# expansion_module_BLE_BMD330AR.net
KiCad netlist of a schematic drawn in EAGLE
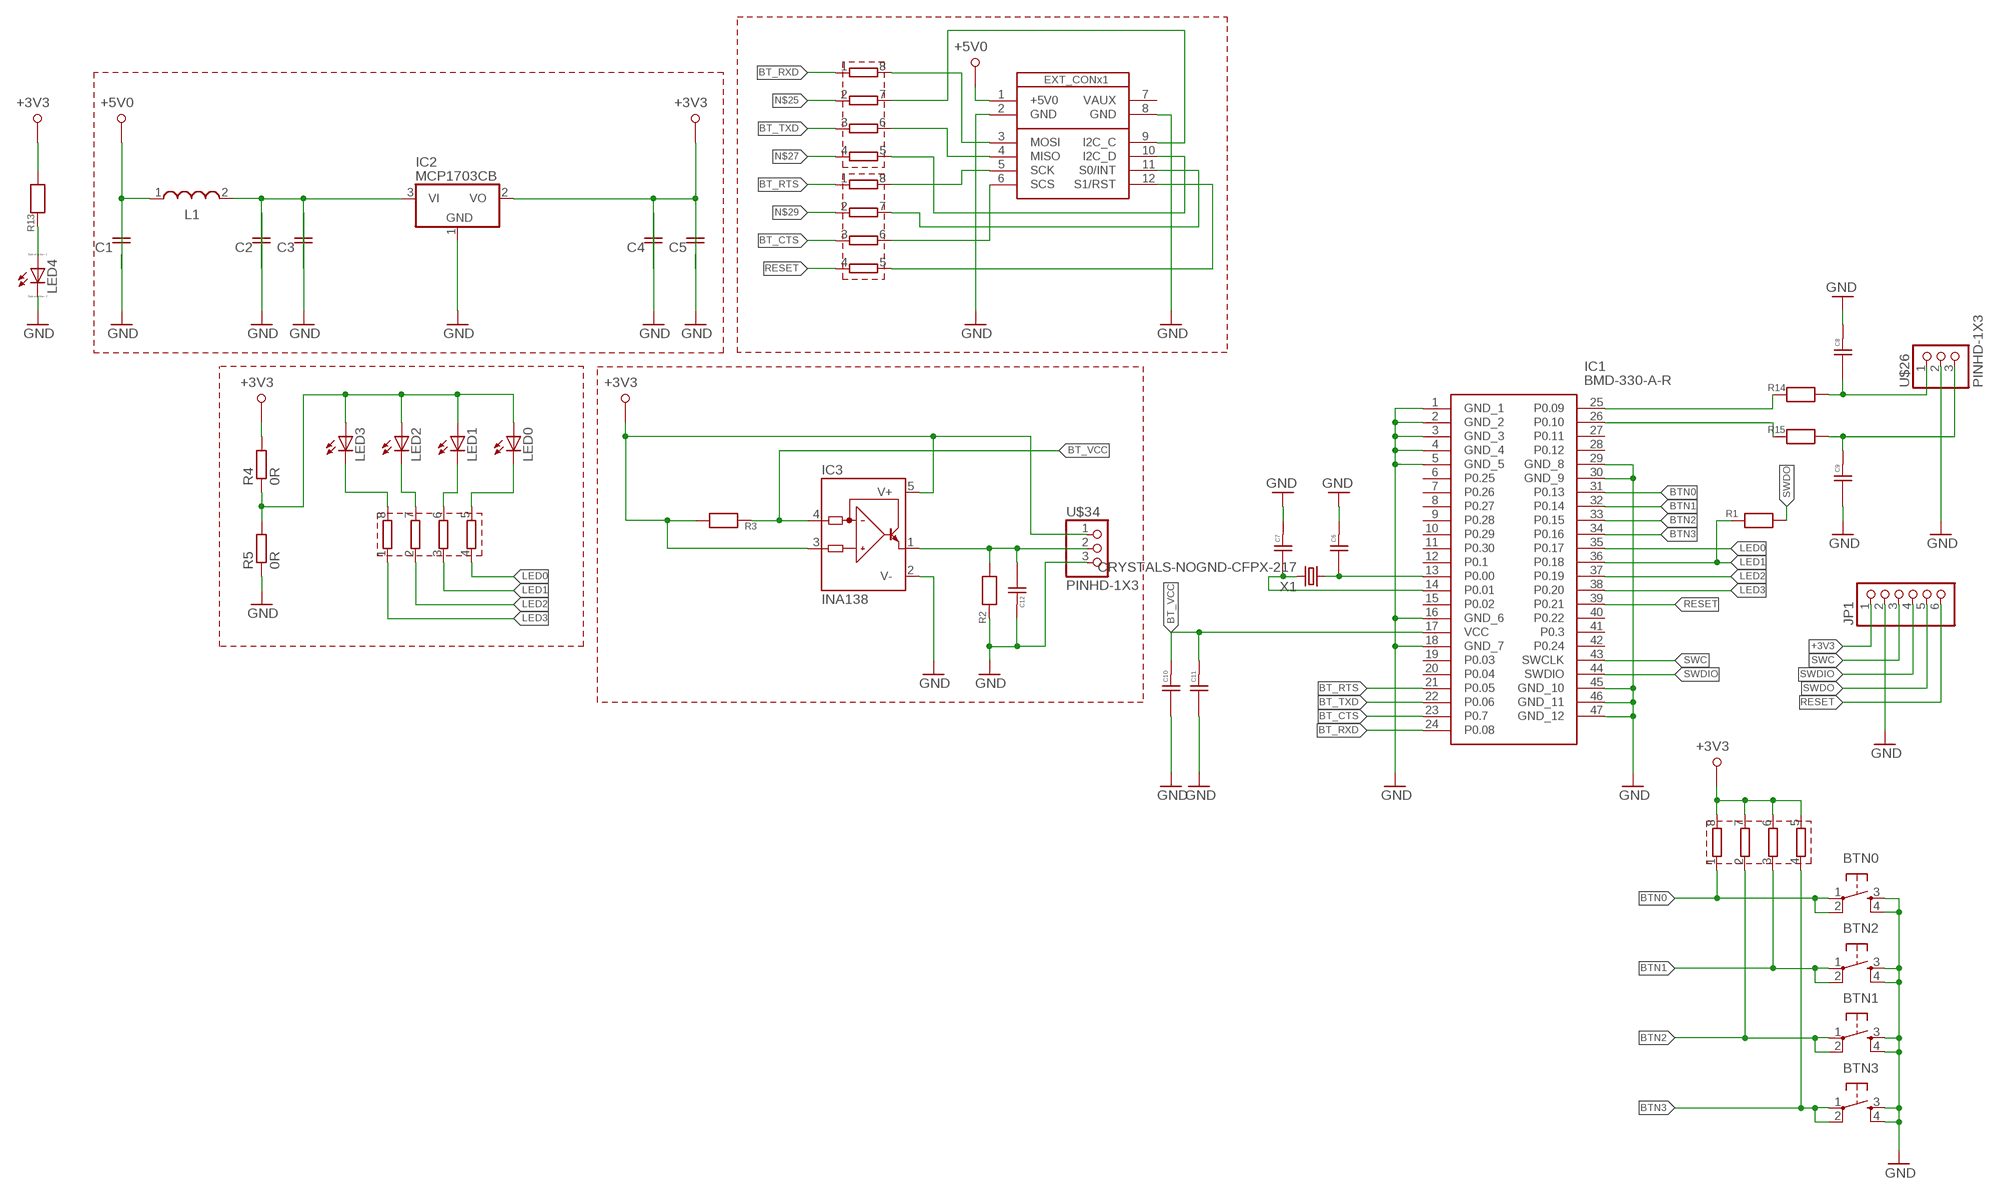
[diagram p0: schematic, sheet 1]

(export (version "E")
  (design (tool "Eeschema 10.0.6"))
  (components
    (comp (ref "BTN0")
      (value "TACT-SWITCH-SMD_KMR2")
      (footprint "eagle-import:KMR2")
      (libsource (lib "eagle-import") (part "TACT-SWITCH-SMD_KMR2"))
    )
    (comp (ref "BTN1")
      (value "TACT-SWITCH-SMD_KMR2")
      (footprint "eagle-import:KMR2")
      (libsource (lib "eagle-import") (part "TACT-SWITCH-SMD_KMR2"))
    )
    (comp (ref "BTN2")
      (value "TACT-SWITCH-SMD_KMR2")
      (footprint "eagle-import:KMR2")
      (libsource (lib "eagle-import") (part "TACT-SWITCH-SMD_KMR2"))
    )
    (comp (ref "BTN3")
      (value "TACT-SWITCH-SMD_KMR2")
      (footprint "eagle-import:KMR2")
      (libsource (lib "eagle-import") (part "TACT-SWITCH-SMD_KMR2"))
    )
    (comp (ref "C1")
      (value "CAPACITOR_CERAMIC_0402")
      (footprint "eagle-import:CAPACITOR_0402")
      (libsource (lib "eagle-import") (part "CAPACITOR_CERAMIC_0402"))
    )
    (comp (ref "C2")
      (value "CAPACITOR_CERAMIC_0402")
      (footprint "eagle-import:CAPACITOR_0402")
      (libsource (lib "eagle-import") (part "CAPACITOR_CERAMIC_0402"))
    )
    (comp (ref "C3")
      (value "CAPACITOR_CERAMIC_0402")
      (footprint "eagle-import:CAPACITOR_0402")
      (libsource (lib "eagle-import") (part "CAPACITOR_CERAMIC_0402"))
    )
    (comp (ref "C4")
      (value "CAPACITOR_CERAMIC_0402")
      (footprint "eagle-import:CAPACITOR_0402")
      (libsource (lib "eagle-import") (part "CAPACITOR_CERAMIC_0402"))
    )
    (comp (ref "C5")
      (value "CAPACITOR_CERAMIC_0402")
      (footprint "eagle-import:CAPACITOR_0402")
      (libsource (lib "eagle-import") (part "CAPACITOR_CERAMIC_0402"))
    )
    (comp (ref "C6")
      (value "CAPACITOR_CERAMIC_0402")
      (footprint "eagle-import:CAPACITOR_0402")
      (libsource (lib "eagle-import") (part "CAPACITOR_CERAMIC_0402"))
    )
    (comp (ref "C7")
      (value "CAPACITOR_CERAMIC_0402")
      (footprint "eagle-import:CAPACITOR_0402")
      (libsource (lib "eagle-import") (part "CAPACITOR_CERAMIC_0402"))
    )
    (comp (ref "C8")
      (value "CAPACITOR_CERAMIC_0402")
      (footprint "eagle-import:CAPACITOR_0402")
      (libsource (lib "eagle-import") (part "CAPACITOR_CERAMIC_0402"))
    )
    (comp (ref "C9")
      (value "CAPACITOR_CERAMIC_0402")
      (footprint "eagle-import:CAPACITOR_0402")
      (libsource (lib "eagle-import") (part "CAPACITOR_CERAMIC_0402"))
    )
    (comp (ref "C10")
      (value "CAPACITOR_CERAMIC_0402")
      (footprint "eagle-import:CAPACITOR_0402")
      (libsource (lib "eagle-import") (part "CAPACITOR_CERAMIC_0402"))
    )
    (comp (ref "C11")
      (value "CAPACITOR_CERAMIC_0402")
      (footprint "eagle-import:CAPACITOR_0402")
      (libsource (lib "eagle-import") (part "CAPACITOR_CERAMIC_0402"))
    )
    (comp (ref "C12")
      (value "CAPACITOR_CERAMIC_0402")
      (footprint "eagle-import:CAPACITOR_0402")
      (libsource (lib "eagle-import") (part "CAPACITOR_CERAMIC_0402"))
    )
    (comp (ref "IC1")
      (value "BMD-330-A-R")
      (footprint "eagle-import:BMD-300")
      (fields (field (name "MOUSER_PART_NUMBER") "377-BMD-330-A-R"))
      (libsource (lib "eagle-import") (part "BMD-330-A-R"))
    )
    (comp (ref "IC2")
      (value "MCP1703CB")
      (footprint "eagle-import:SOT23")
      (libsource (lib "eagle-import") (part "MCP1703CB"))
    )
    (comp (ref "IC3")
      (value "INA138")
      (footprint "eagle-import:SOT23-5")
      (fields (field (name "MF") "TEXAS INSTRUMENTS") (field (name "MPN") "INA138NA/250"))
      (libsource (lib "eagle-import") (part "INA138"))
    )
    (comp (ref "JP1")
      (value "PINHD-1X6")
      (footprint "eagle-import:1X06")
      (libsource (lib "eagle-import") (part "PINHD-1X6"))
    )
    (comp (ref "L1")
      (value "WE-LQ_1210")
      (footprint "eagle-import:WE-LQ_M")
      (libsource (lib "eagle-import") (part "WE-LQ_1210"))
    )
    (comp (ref "LED0")
      (value "LEDSML0603")
      (footprint "eagle-import:SML0603")
      (libsource (lib "eagle-import") (part "LEDSML0603"))
    )
    (comp (ref "LED1")
      (value "LEDSML0603")
      (footprint "eagle-import:SML0603")
      (libsource (lib "eagle-import") (part "LEDSML0603"))
    )
    (comp (ref "LED2")
      (value "LEDSML0603")
      (footprint "eagle-import:SML0603")
      (libsource (lib "eagle-import") (part "LEDSML0603"))
    )
    (comp (ref "LED3")
      (value "LEDSML0603")
      (footprint "eagle-import:SML0603")
      (libsource (lib "eagle-import") (part "LEDSML0603"))
    )
    (comp (ref "LED4")
      (value "LED_ESML0603")
      (footprint "eagle-import:LED_SML0603")
      (libsource (lib "eagle-import") (part "LED_ESML0603"))
    )
    (comp (ref "R1")
      (value "RESISTOR_0402")
      (footprint "eagle-import:RESISITOR_0402")
      (libsource (lib "eagle-import") (part "vb_RLCD_RESISTOR_0402"))
    )
    (comp (ref "R2")
      (value "RESISTOR_0402")
      (footprint "eagle-import:RESISITOR_0402")
      (libsource (lib "eagle-import") (part "vb_RLCD_RESISTOR_0402"))
    )
    (comp (ref "R3")
      (value "RESISTOR_0402")
      (footprint "eagle-import:RESISITOR_0402")
      (libsource (lib "eagle-import") (part "vb_RLCD_RESISTOR_0402"))
    )
    (comp (ref "R4")
      (value "0R")
      (footprint "eagle-import:R0603")
      (libsource (lib "eagle-import") (part "R-EU_R0603"))
    )
    (comp (ref "R5")
      (value "0R")
      (footprint "eagle-import:R0603")
      (libsource (lib "eagle-import") (part "R-EU_R0603"))
    )
    (comp (ref "R13")
      (value "RESISTOR_0402")
      (footprint "eagle-import:RESISITOR_0402")
      (libsource (lib "eagle-import") (part "RESISTOR_0402"))
    )
    (comp (ref "R14")
      (value "RESISTOR_0402")
      (footprint "eagle-import:RESISITOR_0402")
      (libsource (lib "eagle-import") (part "vb_RLCD_RESISTOR_0402"))
    )
    (comp (ref "R15")
      (value "RESISTOR_0402")
      (footprint "eagle-import:RESISITOR_0402")
      (libsource (lib "eagle-import") (part "vb_RLCD_RESISTOR_0402"))
    )
    (comp (ref "RN1")
      (value "RESISTOR-DIL_4R-N")
      (footprint "eagle-import:EXB28V")
      (libsource (lib "eagle-import") (part "RESISTOR-DIL_4R-N"))
    )
    (comp (ref "RN2")
      (value "RESISTOR-DIL_4R-N")
      (footprint "eagle-import:EXB28V")
      (libsource (lib "eagle-import") (part "RESISTOR-DIL_4R-N"))
    )
    (comp (ref "RN3")
      (value "RESISTOR-DIL_4R-N")
      (footprint "eagle-import:EXB28V")
      (libsource (lib "eagle-import") (part "RESISTOR-DIL_4R-N"))
    )
    (comp (ref "RN4")
      (value "RESISTOR-DIL_4R-N")
      (footprint "eagle-import:EXB28V")
      (libsource (lib "eagle-import") (part "RESISTOR-DIL_4R-N"))
    )
    (comp (ref "U$1")
      (value "SB_EXT_CON_X1_SPI")
      (footprint "eagle-import:SB_EXT_CON_X1_FULL")
      (libsource (lib "eagle-import") (part "SB_EXT_CON_X1_SPI"))
    )
    (comp (ref "U$26")
      (value "PINHD-1X3")
      (footprint "eagle-import:1X03")
      (libsource (lib "eagle-import") (part "PINHD-1X3"))
    )
    (comp (ref "U$34")
      (value "PINHD-1X3")
      (footprint "eagle-import:1X03")
      (libsource (lib "eagle-import") (part "PINHD-1X3"))
    )
    (comp (ref "X1")
      (value "CRYSTALS-NOGND-CFPX-217")
      (footprint "eagle-import:3.2X1.5-2-PAD")
      (libsource (lib "eagle-import") (part "CRYSTALS-NOGND-CFPX-217"))
    )
  )
  (nets
    (net (code "1") (name "+3V3") (class "Default")
      (node (ref "C4") (pin "2") (pinfunction "2_2") (pintype "passive"))
      (node (ref "C5") (pin "2") (pinfunction "2_2") (pintype "passive"))
      (node (ref "IC2") (pin "2") (pinfunction "VO_2") (pintype "passive"))
      (node (ref "IC3") (pin "3") (pinfunction "IN+_3") (pintype "input"))
      (node (ref "IC3") (pin "5") (pinfunction "V+_5") (pintype "power_in"))
      (node (ref "JP1") (pin "1") (pinfunction "1_1") (pintype "passive"))
      (node (ref "R13") (pin "2") (pinfunction "2_2") (pintype "passive"))
      (node (ref "R3") (pin "2") (pinfunction "2_2") (pintype "passive"))
      (node (ref "R4") (pin "2") (pinfunction "2_2") (pintype "passive"))
      (node (ref "RN4") (pin "5") (pinfunction "5_5") (pintype "passive"))
      (node (ref "RN4") (pin "6") (pinfunction "6_6") (pintype "passive"))
      (node (ref "RN4") (pin "7") (pinfunction "7_7") (pintype "passive"))
      (node (ref "RN4") (pin "8") (pinfunction "8_8") (pintype "passive"))
      (node (ref "U$34") (pin "1") (pinfunction "1_1") (pintype "passive"))
    )
    (net (code "2") (name "+5V0") (class "Default")
      (node (ref "C1") (pin "2") (pinfunction "2_2") (pintype "passive"))
      (node (ref "L1") (pin "1") (pinfunction "1_1") (pintype "passive"))
      (node (ref "U$1") (pin "1") (pinfunction "+5V0_1") (pintype "bidirectional"))
    )
    (net (code "3") (name "BTN0") (class "Default")
      (node (ref "BTN0") (pin "1") (pinfunction "1_1") (pintype "passive"))
      (node (ref "BTN0") (pin "2") (pinfunction "2_2") (pintype "passive"))
      (node (ref "IC1") (pin "31") (pinfunction "P0.13_31") (pintype "bidirectional"))
      (node (ref "RN4") (pin "1") (pinfunction "1_1") (pintype "passive"))
    )
    (net (code "4") (name "BTN1") (class "Default")
      (node (ref "BTN2") (pin "1") (pinfunction "1_1") (pintype "passive"))
      (node (ref "BTN2") (pin "2") (pinfunction "2_2") (pintype "passive"))
      (node (ref "IC1") (pin "32") (pinfunction "P0.14_32") (pintype "bidirectional"))
      (node (ref "RN4") (pin "3") (pinfunction "3_3") (pintype "passive"))
    )
    (net (code "5") (name "BTN2") (class "Default")
      (node (ref "BTN1") (pin "1") (pinfunction "1_1") (pintype "passive"))
      (node (ref "BTN1") (pin "2") (pinfunction "2_2") (pintype "passive"))
      (node (ref "IC1") (pin "33") (pinfunction "P0.15_33") (pintype "bidirectional"))
      (node (ref "RN4") (pin "2") (pinfunction "2_2") (pintype "passive"))
    )
    (net (code "6") (name "BTN3") (class "Default")
      (node (ref "BTN3") (pin "1") (pinfunction "1_1") (pintype "passive"))
      (node (ref "BTN3") (pin "2") (pinfunction "2_2") (pintype "passive"))
      (node (ref "IC1") (pin "34") (pinfunction "P0.16_34") (pintype "bidirectional"))
      (node (ref "RN4") (pin "4") (pinfunction "4_4") (pintype "passive"))
    )
    (net (code "7") (name "BT_CTS") (class "Default")
      (node (ref "IC1") (pin "23") (pinfunction "P0.7_23") (pintype "bidirectional"))
      (node (ref "RN1") (pin "3") (pinfunction "3_3") (pintype "passive"))
    )
    (net (code "8") (name "BT_RTS") (class "Default")
      (node (ref "IC1") (pin "21") (pinfunction "P0.05_21") (pintype "bidirectional"))
      (node (ref "RN1") (pin "1") (pinfunction "1_1") (pintype "passive"))
    )
    (net (code "9") (name "BT_RXD") (class "Default")
      (node (ref "IC1") (pin "24") (pinfunction "P0.08_24") (pintype "bidirectional"))
      (node (ref "RN2") (pin "1") (pinfunction "1_1") (pintype "passive"))
    )
    (net (code "10") (name "BT_TXD") (class "Default")
      (node (ref "IC1") (pin "22") (pinfunction "P0.06_22") (pintype "bidirectional"))
      (node (ref "RN2") (pin "3") (pinfunction "3_3") (pintype "passive"))
    )
    (net (code "11") (name "BT_VCC") (class "Default")
      (node (ref "C10") (pin "2") (pinfunction "2_2") (pintype "passive"))
      (node (ref "C11") (pin "2") (pinfunction "2_2") (pintype "passive"))
      (node (ref "IC1") (pin "17") (pinfunction "VCC_17") (pintype "power_in"))
      (node (ref "IC3") (pin "4") (pinfunction "IN-_4") (pintype "input"))
      (node (ref "R3") (pin "1") (pinfunction "1_1") (pintype "passive"))
    )
    (net (code "12") (name "GND") (class "Default")
      (node (ref "BTN0") (pin "3") (pinfunction "3_3") (pintype "passive"))
      (node (ref "BTN0") (pin "4") (pinfunction "4_4") (pintype "passive"))
      (node (ref "BTN1") (pin "3") (pinfunction "3_3") (pintype "passive"))
      (node (ref "BTN1") (pin "4") (pinfunction "4_4") (pintype "passive"))
      (node (ref "BTN2") (pin "3") (pinfunction "3_3") (pintype "passive"))
      (node (ref "BTN2") (pin "4") (pinfunction "4_4") (pintype "passive"))
      (node (ref "BTN3") (pin "3") (pinfunction "3_3") (pintype "passive"))
      (node (ref "BTN3") (pin "4") (pinfunction "4_4") (pintype "passive"))
      (node (ref "C1") (pin "1") (pinfunction "1_1") (pintype "passive"))
      (node (ref "C10") (pin "1") (pinfunction "1_1") (pintype "passive"))
      (node (ref "C11") (pin "1") (pinfunction "1_1") (pintype "passive"))
      (node (ref "C12") (pin "2") (pinfunction "2_2") (pintype "passive"))
      (node (ref "C2") (pin "1") (pinfunction "1_1") (pintype "passive"))
      (node (ref "C3") (pin "1") (pinfunction "1_1") (pintype "passive"))
      (node (ref "C4") (pin "1") (pinfunction "1_1") (pintype "passive"))
      (node (ref "C5") (pin "1") (pinfunction "1_1") (pintype "passive"))
      (node (ref "C6") (pin "2") (pinfunction "2_2") (pintype "passive"))
      (node (ref "C7") (pin "2") (pinfunction "2_2") (pintype "passive"))
      (node (ref "C8") (pin "2") (pinfunction "2_2") (pintype "passive"))
      (node (ref "C9") (pin "1") (pinfunction "1_1") (pintype "passive"))
      (node (ref "IC1") (pin "1") (pinfunction "GND_1_1") (pintype "bidirectional"))
      (node (ref "IC1") (pin "16") (pinfunction "GND_6_16") (pintype "bidirectional"))
      (node (ref "IC1") (pin "18") (pinfunction "GND_7_18") (pintype "bidirectional"))
      (node (ref "IC1") (pin "2") (pinfunction "GND_2_2") (pintype "bidirectional"))
      (node (ref "IC1") (pin "29") (pinfunction "GND_8_29") (pintype "bidirectional"))
      (node (ref "IC1") (pin "3") (pinfunction "GND_3_3") (pintype "bidirectional"))
      (node (ref "IC1") (pin "30") (pinfunction "GND_9_30") (pintype "bidirectional"))
      (node (ref "IC1") (pin "4") (pinfunction "GND_4_4") (pintype "bidirectional"))
      (node (ref "IC1") (pin "45") (pinfunction "GND_10_45") (pintype "bidirectional"))
      (node (ref "IC1") (pin "46") (pinfunction "GND_11_46") (pintype "bidirectional"))
      (node (ref "IC1") (pin "47") (pinfunction "GND_12_47") (pintype "bidirectional"))
      (node (ref "IC1") (pin "5") (pinfunction "GND_5_5") (pintype "bidirectional"))
      (node (ref "IC2") (pin "1") (pinfunction "GND_1") (pintype "passive"))
      (node (ref "IC3") (pin "2") (pinfunction "V-_2") (pintype "power_in"))
      (node (ref "JP1") (pin "2") (pinfunction "2_2") (pintype "passive"))
      (node (ref "LED4") (pin "C") (pinfunction "C_C") (pintype "passive"))
      (node (ref "R2") (pin "1") (pinfunction "1_1") (pintype "passive"))
      (node (ref "R5") (pin "1") (pinfunction "1_1") (pintype "passive"))
      (node (ref "U$1") (pin "2") (pinfunction "GND_2") (pintype "bidirectional"))
      (node (ref "U$1") (pin "8") (pinfunction "GND_8") (pintype "bidirectional"))
      (node (ref "U$26") (pin "2") (pinfunction "2_2") (pintype "passive"))
      (node (ref "U$34") (pin "3") (pinfunction "3_3") (pintype "passive"))
    )
    (net (code "13") (name "LED0") (class "Default")
      (node (ref "IC1") (pin "35") (pinfunction "P0.17_35") (pintype "bidirectional"))
      (node (ref "RN3") (pin "4") (pinfunction "4_4") (pintype "passive"))
    )
    (net (code "14") (name "LED1") (class "Default")
      (node (ref "IC1") (pin "36") (pinfunction "P0.18_36") (pintype "bidirectional"))
      (node (ref "R1") (pin "1") (pinfunction "1_1") (pintype "passive"))
      (node (ref "RN3") (pin "3") (pinfunction "3_3") (pintype "passive"))
    )
    (net (code "15") (name "LED2") (class "Default")
      (node (ref "IC1") (pin "37") (pinfunction "P0.19_37") (pintype "bidirectional"))
      (node (ref "RN3") (pin "2") (pinfunction "2_2") (pintype "passive"))
    )
    (net (code "16") (name "LED3") (class "Default")
      (node (ref "IC1") (pin "38") (pinfunction "P0.20_38") (pintype "bidirectional"))
      (node (ref "RN3") (pin "1") (pinfunction "1_1") (pintype "passive"))
    )
    (net (code "17") (name "N$25") (class "Default")
      (node (ref "RN2") (pin "2") (pinfunction "2_2") (pintype "passive"))
    )
    (net (code "18") (name "N$27") (class "Default")
      (node (ref "RN2") (pin "4") (pinfunction "4_4") (pintype "passive"))
    )
    (net (code "19") (name "N$29") (class "Default")
      (node (ref "RN1") (pin "2") (pinfunction "2_2") (pintype "passive"))
    )
    (net (code "20") (name "Net-(C8-Pad1)") (class "Default")
      (node (ref "C8") (pin "1") (pinfunction "1_1") (pintype "passive"))
      (node (ref "R14") (pin "2") (pinfunction "2_2") (pintype "passive"))
      (node (ref "U$26") (pin "1") (pinfunction "1_1") (pintype "passive"))
    )
    (net (code "21") (name "Net-(C9-Pad2)") (class "Default")
      (node (ref "C9") (pin "2") (pinfunction "2_2") (pintype "passive"))
      (node (ref "R15") (pin "2") (pinfunction "2_2") (pintype "passive"))
      (node (ref "U$26") (pin "3") (pinfunction "3_3") (pintype "passive"))
    )
    (net (code "22") (name "Net-(IC1-P0.00)") (class "Default")
      (node (ref "C6") (pin "1") (pinfunction "1_1") (pintype "passive"))
      (node (ref "IC1") (pin "13") (pinfunction "P0.00_13") (pintype "bidirectional"))
      (node (ref "X1") (pin "1") (pinfunction "1_1") (pintype "passive"))
    )
    (net (code "23") (name "Net-(IC1-P0.01)") (class "Default")
      (node (ref "C7") (pin "1") (pinfunction "1_1") (pintype "passive"))
      (node (ref "IC1") (pin "14") (pinfunction "P0.01_14") (pintype "bidirectional"))
      (node (ref "X1") (pin "2") (pinfunction "2_2") (pintype "passive"))
    )
    (net (code "24") (name "Net-(IC1-P0.09)") (class "Default")
      (node (ref "IC1") (pin "25") (pinfunction "P0.09_25") (pintype "bidirectional"))
      (node (ref "R14") (pin "1") (pinfunction "1_1") (pintype "passive"))
    )
    (net (code "25") (name "Net-(IC1-P0.10)") (class "Default")
      (node (ref "IC1") (pin "26") (pinfunction "P0.10_26") (pintype "bidirectional"))
      (node (ref "R15") (pin "1") (pinfunction "1_1") (pintype "passive"))
    )
    (net (code "26") (name "Net-(IC2-VI)") (class "Default")
      (node (ref "C2") (pin "2") (pinfunction "2_2") (pintype "passive"))
      (node (ref "C3") (pin "2") (pinfunction "2_2") (pintype "passive"))
      (node (ref "IC2") (pin "3") (pinfunction "VI_3") (pintype "input"))
      (node (ref "L1") (pin "2") (pinfunction "2_2") (pintype "passive"))
    )
    (net (code "27") (name "Net-(IC3-OUT)") (class "Default")
      (node (ref "C12") (pin "1") (pinfunction "1_1") (pintype "passive"))
      (node (ref "IC3") (pin "1") (pinfunction "OUT_1") (pintype "output"))
      (node (ref "R2") (pin "2") (pinfunction "2_2") (pintype "passive"))
      (node (ref "U$34") (pin "2") (pinfunction "2_2") (pintype "passive"))
    )
    (net (code "28") (name "Net-(LED0-PadA)") (class "Default")
      (node (ref "LED0") (pin "A") (pinfunction "A_A") (pintype "passive"))
      (node (ref "LED1") (pin "A") (pinfunction "A_A") (pintype "passive"))
      (node (ref "LED2") (pin "A") (pinfunction "A_A") (pintype "passive"))
      (node (ref "LED3") (pin "A") (pinfunction "A_A") (pintype "passive"))
      (node (ref "R4") (pin "1") (pinfunction "1_1") (pintype "passive"))
      (node (ref "R5") (pin "2") (pinfunction "2_2") (pintype "passive"))
    )
    (net (code "29") (name "Net-(LED0-PadC)") (class "Default")
      (node (ref "LED0") (pin "C") (pinfunction "C_C") (pintype "passive"))
      (node (ref "RN3") (pin "5") (pinfunction "5_5") (pintype "passive"))
    )
    (net (code "30") (name "Net-(LED1-PadC)") (class "Default")
      (node (ref "LED1") (pin "C") (pinfunction "C_C") (pintype "passive"))
      (node (ref "RN3") (pin "6") (pinfunction "6_6") (pintype "passive"))
    )
    (net (code "31") (name "Net-(LED2-PadC)") (class "Default")
      (node (ref "LED2") (pin "C") (pinfunction "C_C") (pintype "passive"))
      (node (ref "RN3") (pin "7") (pinfunction "7_7") (pintype "passive"))
    )
    (net (code "32") (name "Net-(LED3-PadC)") (class "Default")
      (node (ref "LED3") (pin "C") (pinfunction "C_C") (pintype "passive"))
      (node (ref "RN3") (pin "8") (pinfunction "8_8") (pintype "passive"))
    )
    (net (code "33") (name "Net-(LED4-PadA)") (class "Default")
      (node (ref "LED4") (pin "A") (pinfunction "A_A") (pintype "passive"))
      (node (ref "R13") (pin "1") (pinfunction "1_1") (pintype "passive"))
    )
    (net (code "34") (name "Net-(U$1-I2C_C)") (class "Default")
      (node (ref "RN2") (pin "7") (pinfunction "7_7") (pintype "passive"))
      (node (ref "U$1") (pin "9") (pinfunction "I2C_C_9") (pintype "bidirectional"))
    )
    (net (code "35") (name "Net-(U$1-I2C_D)") (class "Default")
      (node (ref "RN2") (pin "5") (pinfunction "5_5") (pintype "passive"))
      (node (ref "U$1") (pin "10") (pinfunction "I2C_D_10") (pintype "bidirectional"))
    )
    (net (code "36") (name "Net-(U$1-MISO)") (class "Default")
      (node (ref "RN2") (pin "6") (pinfunction "6_6") (pintype "passive"))
      (node (ref "U$1") (pin "4") (pinfunction "MISO_4") (pintype "bidirectional"))
    )
    (net (code "37") (name "Net-(U$1-MOSI)") (class "Default")
      (node (ref "RN2") (pin "8") (pinfunction "8_8") (pintype "passive"))
      (node (ref "U$1") (pin "3") (pinfunction "MOSI_3") (pintype "bidirectional"))
    )
    (net (code "38") (name "Net-(U$1-S0{slash}INT)") (class "Default")
      (node (ref "RN1") (pin "7") (pinfunction "7_7") (pintype "passive"))
      (node (ref "U$1") (pin "11") (pinfunction "S0/INT_11") (pintype "bidirectional"))
    )
    (net (code "39") (name "Net-(U$1-S1{slash}RST)") (class "Default")
      (node (ref "RN1") (pin "5") (pinfunction "5_5") (pintype "passive"))
      (node (ref "U$1") (pin "12") (pinfunction "S1/RST_12") (pintype "bidirectional"))
    )
    (net (code "40") (name "Net-(U$1-SCK)") (class "Default")
      (node (ref "RN1") (pin "8") (pinfunction "8_8") (pintype "passive"))
      (node (ref "U$1") (pin "5") (pinfunction "SCK_5") (pintype "bidirectional"))
    )
    (net (code "41") (name "Net-(U$1-SCS)") (class "Default")
      (node (ref "RN1") (pin "6") (pinfunction "6_6") (pintype "passive"))
      (node (ref "U$1") (pin "6") (pinfunction "SCS_6") (pintype "bidirectional"))
    )
    (net (code "42") (name "RESET") (class "Default")
      (node (ref "IC1") (pin "39") (pinfunction "P0.21_39") (pintype "bidirectional"))
      (node (ref "JP1") (pin "6") (pinfunction "6_6") (pintype "passive"))
      (node (ref "RN1") (pin "4") (pinfunction "4_4") (pintype "passive"))
    )
    (net (code "43") (name "SWC") (class "Default")
      (node (ref "IC1") (pin "43") (pinfunction "SWCLK_43") (pintype "bidirectional"))
      (node (ref "JP1") (pin "3") (pinfunction "3_3") (pintype "passive"))
    )
    (net (code "44") (name "SWDIO") (class "Default")
      (node (ref "IC1") (pin "44") (pinfunction "SWDIO_44") (pintype "bidirectional"))
      (node (ref "JP1") (pin "4") (pinfunction "4_4") (pintype "passive"))
    )
    (net (code "45") (name "SWDO") (class "Default")
      (node (ref "JP1") (pin "5") (pinfunction "5_5") (pintype "passive"))
      (node (ref "R1") (pin "2") (pinfunction "2_2") (pintype "passive"))
    )
    (net (code "46") (name "unconnected-(IC1-P0.1-Pad12)") (class "Default")
      (node (ref "IC1") (pin "12") (pinfunction "P0.1_12") (pintype "bidirectional"))
    )
    (net (code "47") (name "unconnected-(IC1-P0.02-Pad15)") (class "Default")
      (node (ref "IC1") (pin "15") (pinfunction "P0.02_15") (pintype "bidirectional"))
    )
    (net (code "48") (name "unconnected-(IC1-P0.03-Pad19)") (class "Default")
      (node (ref "IC1") (pin "19") (pinfunction "P0.03_19") (pintype "bidirectional"))
    )
    (net (code "49") (name "unconnected-(IC1-P0.3-Pad41)") (class "Default")
      (node (ref "IC1") (pin "41") (pinfunction "P0.3_41") (pintype "bidirectional"))
    )
    (net (code "50") (name "unconnected-(IC1-P0.04-Pad20)") (class "Default")
      (node (ref "IC1") (pin "20") (pinfunction "P0.04_20") (pintype "bidirectional"))
    )
    (net (code "51") (name "unconnected-(IC1-P0.11-Pad27)") (class "Default")
      (node (ref "IC1") (pin "27") (pinfunction "P0.11_27") (pintype "bidirectional"))
    )
    (net (code "52") (name "unconnected-(IC1-P0.12-Pad28)") (class "Default")
      (node (ref "IC1") (pin "28") (pinfunction "P0.12_28") (pintype "bidirectional"))
    )
    (net (code "53") (name "unconnected-(IC1-P0.22-Pad40)") (class "Default")
      (node (ref "IC1") (pin "40") (pinfunction "P0.22_40") (pintype "bidirectional"))
    )
    (net (code "54") (name "unconnected-(IC1-P0.24-Pad42)") (class "Default")
      (node (ref "IC1") (pin "42") (pinfunction "P0.24_42") (pintype "bidirectional"))
    )
    (net (code "55") (name "unconnected-(IC1-P0.25-Pad6)") (class "Default")
      (node (ref "IC1") (pin "6") (pinfunction "P0.25_6") (pintype "bidirectional"))
    )
    (net (code "56") (name "unconnected-(IC1-P0.26-Pad7)") (class "Default")
      (node (ref "IC1") (pin "7") (pinfunction "P0.26_7") (pintype "bidirectional"))
    )
    (net (code "57") (name "unconnected-(IC1-P0.27-Pad8)") (class "Default")
      (node (ref "IC1") (pin "8") (pinfunction "P0.27_8") (pintype "bidirectional"))
    )
    (net (code "58") (name "unconnected-(IC1-P0.28-Pad9)") (class "Default")
      (node (ref "IC1") (pin "9") (pinfunction "P0.28_9") (pintype "bidirectional"))
    )
    (net (code "59") (name "unconnected-(IC1-P0.29-Pad10)") (class "Default")
      (node (ref "IC1") (pin "10") (pinfunction "P0.29_10") (pintype "bidirectional"))
    )
    (net (code "60") (name "unconnected-(IC1-P0.30-Pad11)") (class "Default")
      (node (ref "IC1") (pin "11") (pinfunction "P0.30_11") (pintype "bidirectional"))
    )
    (net (code "61") (name "unconnected-(U$1-VAUX-Pad7)") (class "Default")
      (node (ref "U$1") (pin "7") (pinfunction "VAUX_7") (pintype "bidirectional"))
    )
  )
)
